# LED_Light_LEDs.net
KiCad netlist of a schematic drawn in EAGLE
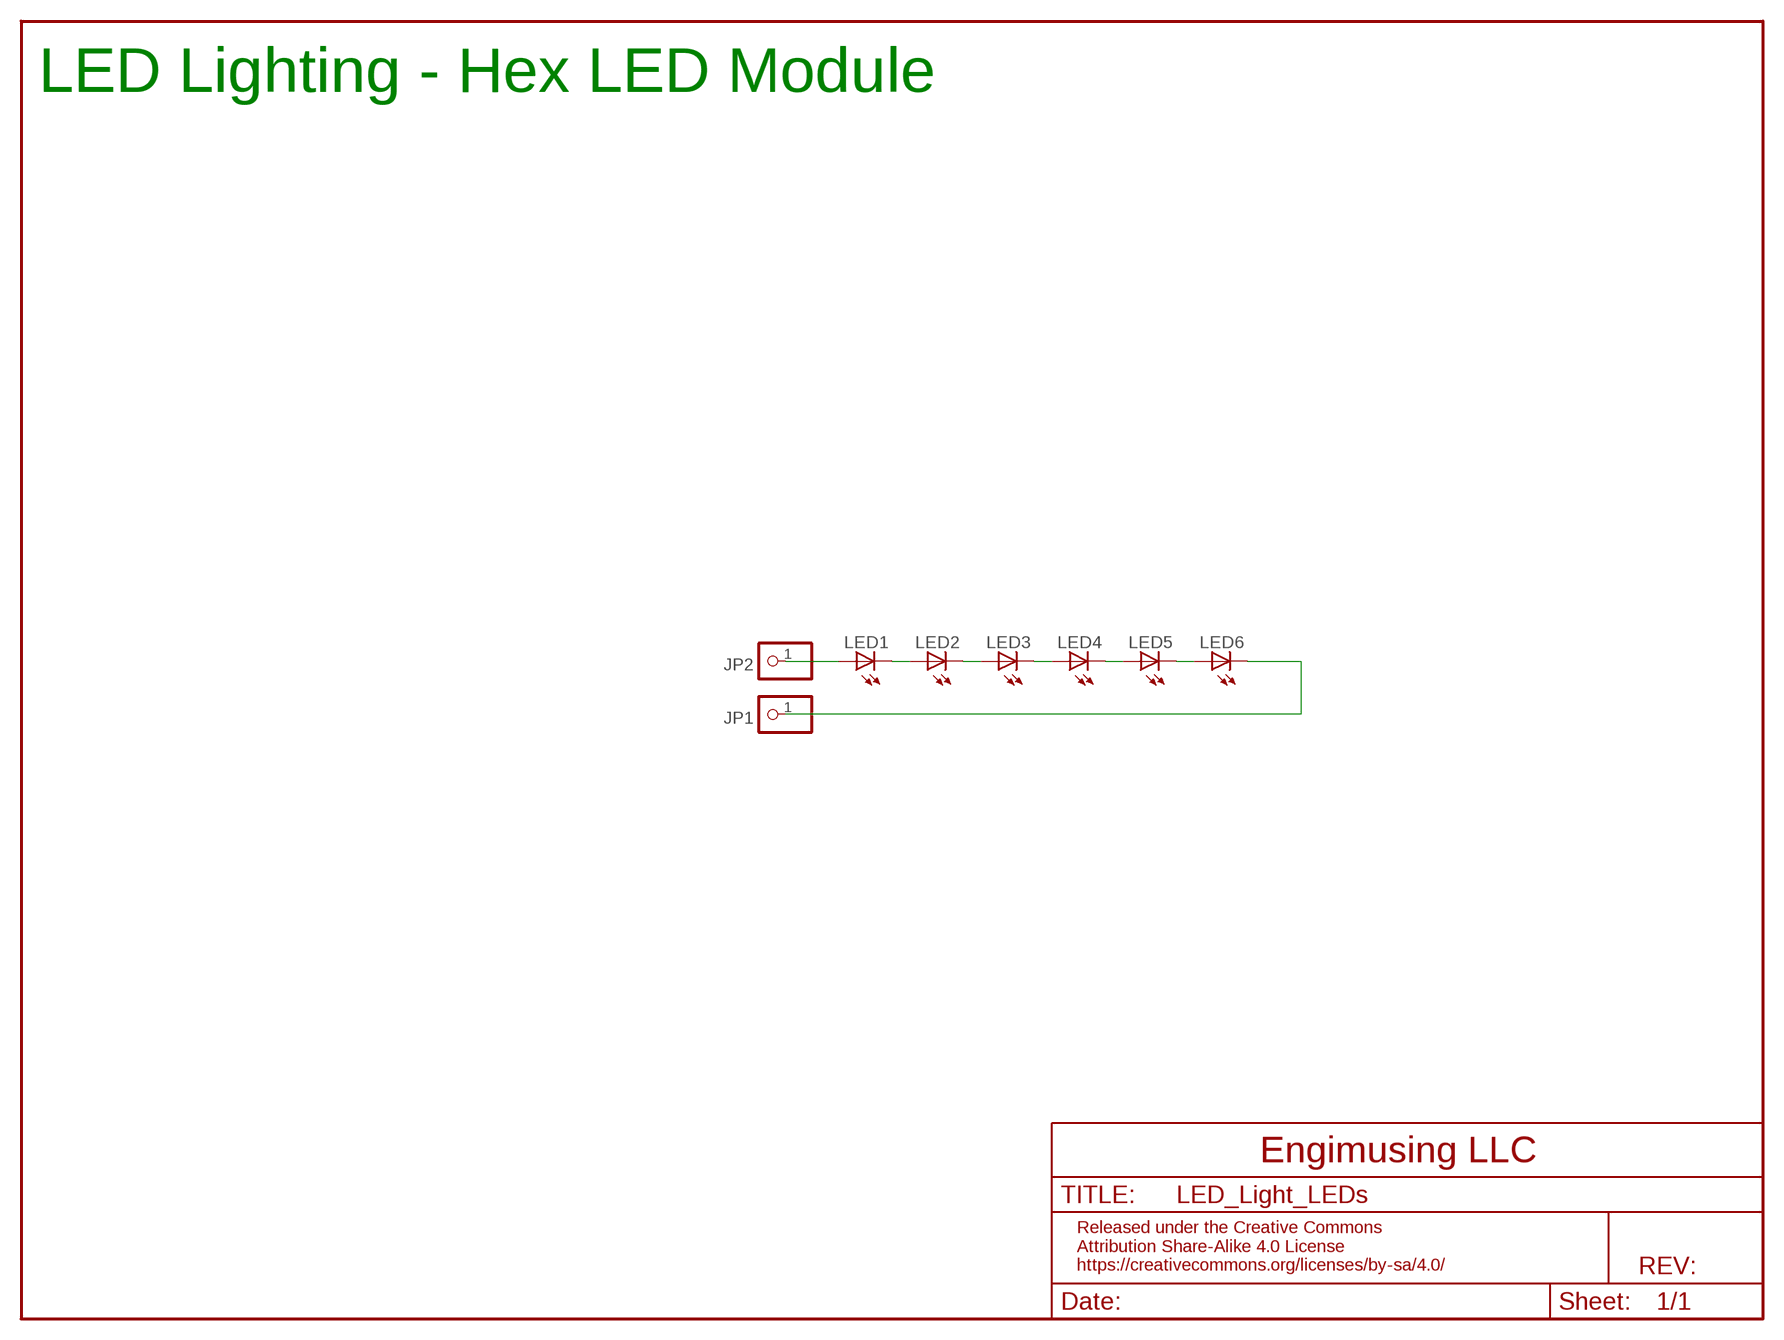
[diagram p0: schematic, sheet 1]

(export (version "E")
  (design (tool "Eeschema 10.0.6"))
  (components
    (comp (ref "JP1")
      (value "PINHD-1X1")
      (footprint "eagle-import:1X01")
      (libsource (lib "eagle-import") (part "PINHD-1X1"))
    )
    (comp (ref "JP2")
      (value "PINHD-1X1")
      (footprint "eagle-import:1X01")
      (libsource (lib "eagle-import") (part "PINHD-1X1"))
    )
    (comp (ref "LED1")
      (value "LED-MX3")
      (footprint "eagle-import:LED_5X5")
      (libsource (lib "eagle-import") (part "LED-MX3"))
    )
    (comp (ref "LED2")
      (value "LED-MX3")
      (footprint "eagle-import:LED_5X5")
      (libsource (lib "eagle-import") (part "LED-MX3"))
    )
    (comp (ref "LED3")
      (value "LED-MX3")
      (footprint "eagle-import:LED_5X5")
      (libsource (lib "eagle-import") (part "LED-MX3"))
    )
    (comp (ref "LED4")
      (value "LED-MX3")
      (footprint "eagle-import:LED_5X5")
      (libsource (lib "eagle-import") (part "LED-MX3"))
    )
    (comp (ref "LED5")
      (value "LED-MX3")
      (footprint "eagle-import:LED_5X5")
      (libsource (lib "eagle-import") (part "LED-MX3"))
    )
    (comp (ref "LED6")
      (value "LED-MX3")
      (footprint "eagle-import:LED_5X5")
      (libsource (lib "eagle-import") (part "LED-MX3"))
    )
  )
  (nets
    (net (code "1") (name "Net-(JP1-Pad1)") (class "Default")
      (node (ref "JP1") (pin "1") (pinfunction "1_1") (pintype "passive"))
      (node (ref "LED6") (pin "C") (pinfunction "C_C") (pintype "passive"))
    )
    (net (code "2") (name "Net-(JP2-Pad1)") (class "Default")
      (node (ref "JP2") (pin "1") (pinfunction "1_1") (pintype "passive"))
      (node (ref "LED1") (pin "A") (pinfunction "A_A") (pintype "passive"))
    )
    (net (code "3") (name "Net-(LED1-PadC)") (class "Default")
      (node (ref "LED1") (pin "C") (pinfunction "C_C") (pintype "passive"))
      (node (ref "LED2") (pin "A") (pinfunction "A_A") (pintype "passive"))
    )
    (net (code "4") (name "Net-(LED2-PadC)") (class "Default")
      (node (ref "LED2") (pin "C") (pinfunction "C_C") (pintype "passive"))
      (node (ref "LED3") (pin "A") (pinfunction "A_A") (pintype "passive"))
    )
    (net (code "5") (name "Net-(LED3-PadC)") (class "Default")
      (node (ref "LED3") (pin "C") (pinfunction "C_C") (pintype "passive"))
      (node (ref "LED4") (pin "A") (pinfunction "A_A") (pintype "passive"))
    )
    (net (code "6") (name "Net-(LED4-PadC)") (class "Default")
      (node (ref "LED4") (pin "C") (pinfunction "C_C") (pintype "passive"))
      (node (ref "LED5") (pin "A") (pinfunction "A_A") (pintype "passive"))
    )
    (net (code "7") (name "Net-(LED5-PadC)") (class "Default")
      (node (ref "LED5") (pin "C") (pinfunction "C_C") (pintype "passive"))
      (node (ref "LED6") (pin "A") (pinfunction "A_A") (pintype "passive"))
    )
  )
)
